# communication.net
KiCad netlist of a schematic drawn in Altium Designer
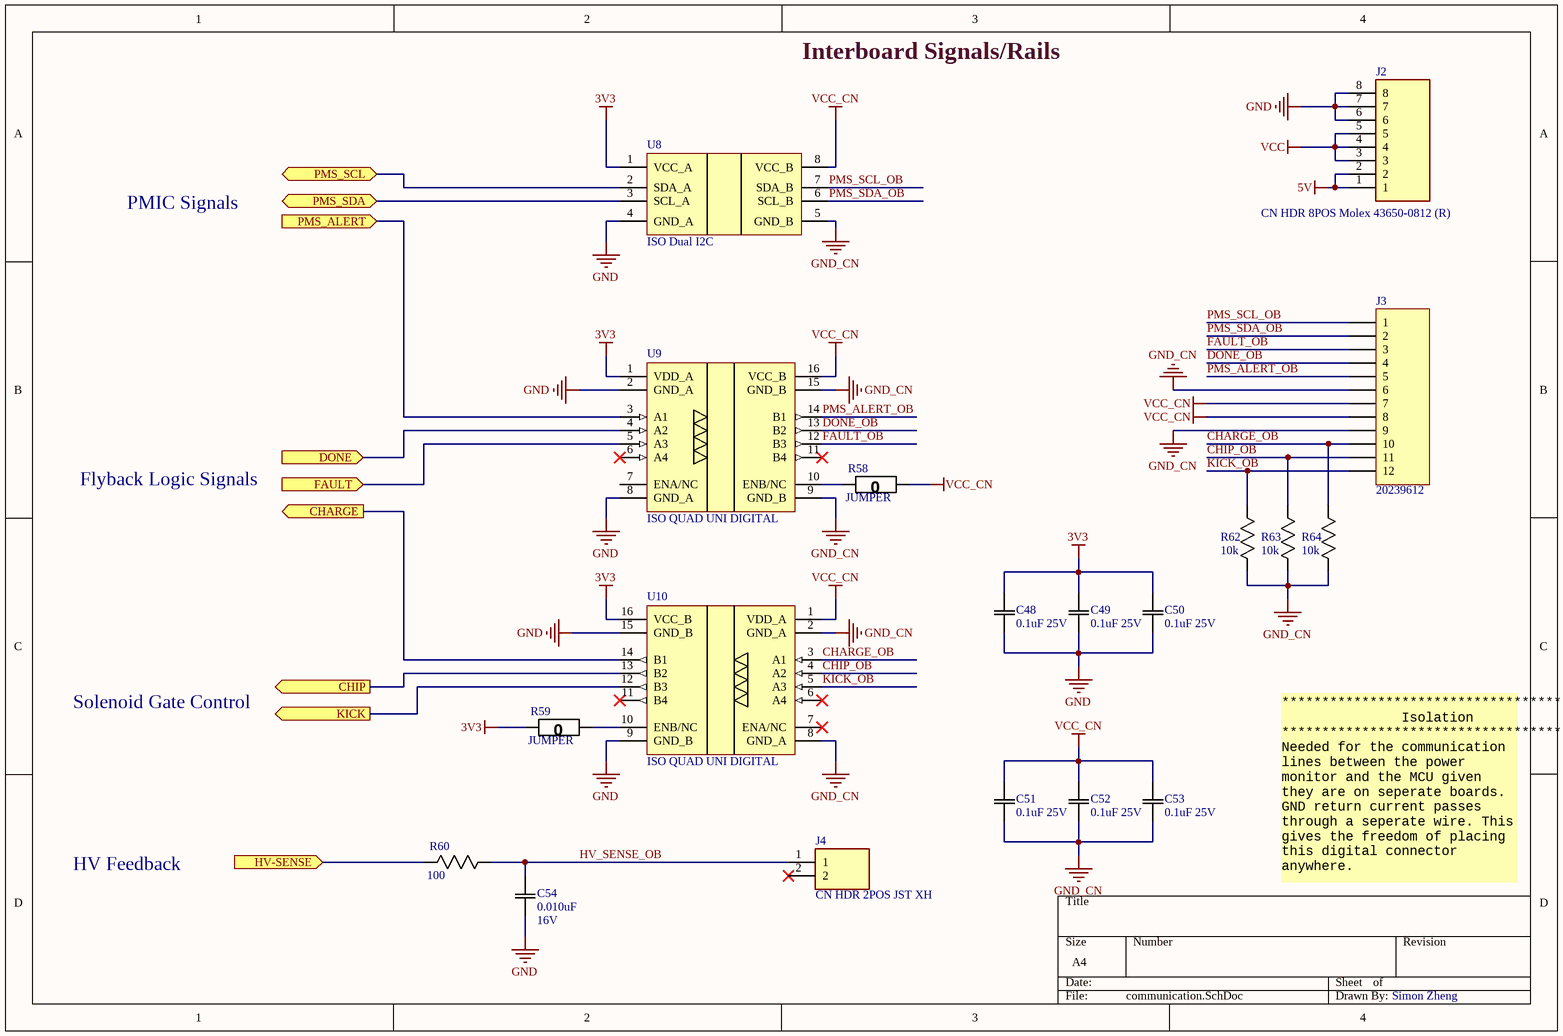
[diagram p0: communication.SchDoc]

(export (version "E")
  (design (tool "Eeschema 10.0.6"))
  (components
    (comp (ref "C48")
      (value "0.1uF 25V")
      (footprint "0805")
      (description "CAP CER 0.1UF 25V X7R 0805")
      (fields (field (name "TOLERANCE") "10%"))
      (libsource (lib "AltiumLibraries") (part "CAP 0.1uF 25V"))
    )
    (comp (ref "C49")
      (value "0.1uF 25V")
      (footprint "0805")
      (description "CAP CER 0.1UF 25V X7R 0805")
      (fields (field (name "TOLERANCE") "10%"))
      (libsource (lib "AltiumLibraries") (part "CAP 0.1uF 25V"))
    )
    (comp (ref "C50")
      (value "0.1uF 25V")
      (footprint "0805")
      (description "CAP CER 0.1UF 25V X7R 0805")
      (fields (field (name "TOLERANCE") "10%"))
      (libsource (lib "AltiumLibraries") (part "CAP 0.1uF 25V"))
    )
    (comp (ref "C51")
      (value "0.1uF 25V")
      (footprint "0805")
      (description "CAP CER 0.1UF 25V X7R 0805")
      (fields (field (name "TOLERANCE") "10%"))
      (libsource (lib "AltiumLibraries") (part "CAP 0.1uF 25V"))
    )
    (comp (ref "C52")
      (value "0.1uF 25V")
      (footprint "0805")
      (description "CAP CER 0.1UF 25V X7R 0805")
      (fields (field (name "TOLERANCE") "10%"))
      (libsource (lib "AltiumLibraries") (part "CAP 0.1uF 25V"))
    )
    (comp (ref "C53")
      (value "0.1uF 25V")
      (footprint "0805")
      (description "CAP CER 0.1UF 25V X7R 0805")
      (fields (field (name "TOLERANCE") "10%"))
      (libsource (lib "AltiumLibraries") (part "CAP 0.1uF 25V"))
    )
    (comp (ref "C54")
      (value "0.010uF")
      (footprint "0805")
      (description "CAP CER 0.010UF 16V X5R 0603/0805")
      (fields (field (name "TOLERANCE") "10%") (field (name "RATING") "16V"))
      (libsource (lib "AltiumLibraries") (part "CAP 0.010uF 16V"))
    )
    (comp (ref "J2")
      (value "CN HDR 8POS Molex 43650-0812 (R)")
      (footprint "CN 43650-0812")
      (description "Molex 43650-0812 8POS Microfit\r\nsingle row, right angle, surface mount")
      (libsource (lib "AltiumLibraries") (part "CN HDR 8POS Molex 43650-0812 (R)"))
    )
    (comp (ref "J3")
      (value "20239612")
      (footprint "CN 20239612")
      (description "12 POS Right Angle Pico Clasp Surface Mount")
      (libsource (lib "AltiumLibraries") (part "CN Pico Clasp 12POS"))
    )
    (comp (ref "J4")
      (value "CN HDR 2POS JST XH")
      (footprint "JST_S2B-XH-A(LF)(SN)")
      (description "Connector Header Through Hole 2 position 0.098 _2.50mm_\r\nJST XH")
      (fields (field (name "MP") "B2B-XH-A_LF__SN_") (field (name "MF") "JST Sales"))
      (libsource (lib "AltiumLibraries") (part "CN HDR 2POS JST XH"))
    )
    (comp (ref "R58")
      (value "JUMPER")
      (footprint "0805")
      (description "RES SMD 0 OHM JUMPER GENERIC 0805")
      (libsource (lib "AltiumLibraries") (part "RES 0 JUMPER"))
    )
    (comp (ref "R59")
      (value "JUMPER")
      (footprint "0805")
      (description "RES SMD 0 OHM JUMPER GENERIC 0805")
      (libsource (lib "AltiumLibraries") (part "RES 0 JUMPER"))
    )
    (comp (ref "R60")
      (value "100")
      (footprint "0805")
      (description "RES SMD 100 OHM 5% 1/8W 0805")
      (fields (field (name "TOLERANCE") "5%"))
      (libsource (lib "AltiumLibraries") (part "RES 100.0 1/8W"))
    )
    (comp (ref "R62")
      (value "10k")
      (footprint "0805")
      (description "RES SMD 10K OHM 1% 1/8W 0805")
      (fields (field (name "TOLERANCE") "1%"))
      (libsource (lib "") (part "RES 10k 1/8W - 1%_1"))
    )
    (comp (ref "R63")
      (value "10k")
      (footprint "0805")
      (description "RES SMD 10K OHM 1% 1/8W 0805")
      (fields (field (name "TOLERANCE") "1%"))
      (libsource (lib "AltiumLibraries") (part "RES 10k 1/8W - 1%"))
    )
    (comp (ref "R64")
      (value "10k")
      (footprint "0805")
      (description "RES SMD 10K OHM 1% 1/8W 0805")
      (fields (field (name "TOLERANCE") "1%"))
      (libsource (lib "AltiumLibraries") (part "RES 10k 1/8W - 1%"))
    )
    (comp (ref "U8")
      (value "ISO Dual I2C")
      (footprint "SOIC127P600X175-8N")
      (description "Digital Isolation Dual Ch Bidirectional I2C")
      (libsource (lib "AltiumLibraries") (part "ISO Dual I2C"))
    )
    (comp (ref "U9")
      (value "ISO QUAD UNI DIGITAL")
      (footprint "SOIC127P600X175-16N")
      (description "Digital Isolation Quad Channel.")
      (libsource (lib "") (part "ISO QUAD UNI DIGITAL_1"))
    )
    (comp (ref "U10")
      (value "ISO QUAD UNI DIGITAL")
      (footprint "SOIC127P600X175-16N")
      (description "Digital Isolation Quad Channel.")
      (libsource (lib "AltiumLibraries") (part "ISO QUAD UNI DIGITAL"))
    )
  )
  (nets
    (net (code "1") (name "/CHARGE") (class "Default")
      (node (ref "U10") (pin "14") (pinfunction "B1_14") (pintype "output"))
    )
    (net (code "2") (name "/CHARGE_OB") (class "Default")
      (node (ref "J3") (pin "10") (pinfunction "10_10") (pintype "passive"))
      (node (ref "R64") (pin "1") (pinfunction "R1_1") (pintype "passive"))
      (node (ref "U10") (pin "3") (pinfunction "A1_3") (pintype "input"))
    )
    (net (code "3") (name "/CHIP") (class "Default")
      (node (ref "U10") (pin "13") (pinfunction "B2_13") (pintype "output"))
    )
    (net (code "4") (name "/CHIP_OB") (class "Default")
      (node (ref "J3") (pin "11") (pinfunction "11_11") (pintype "passive"))
      (node (ref "R63") (pin "1") (pinfunction "R1_1") (pintype "passive"))
      (node (ref "U10") (pin "4") (pinfunction "A2_4") (pintype "input"))
    )
    (net (code "5") (name "/DONE") (class "Default")
      (node (ref "U9") (pin "4") (pinfunction "A2_4") (pintype "input"))
    )
    (net (code "6") (name "/DONE_OB") (class "Default")
      (node (ref "J3") (pin "4") (pinfunction "4_4") (pintype "passive"))
      (node (ref "U9") (pin "13") (pinfunction "B2_13") (pintype "output"))
    )
    (net (code "7") (name "/FAULT") (class "Default")
      (node (ref "U9") (pin "5") (pinfunction "A3_5") (pintype "input"))
    )
    (net (code "8") (name "/FAULT_OB") (class "Default")
      (node (ref "J3") (pin "3") (pinfunction "3_3") (pintype "passive"))
      (node (ref "U9") (pin "12") (pinfunction "B3_12") (pintype "output"))
    )
    (net (code "9") (name "/HV-SENSE") (class "Default")
      (node (ref "R60") (pin "2") (pinfunction "R2_2") (pintype "passive"))
    )
    (net (code "10") (name "/HV_SENSE_OB") (class "Default")
      (node (ref "C54") (pin "1") (pinfunction "C1_1") (pintype "passive"))
      (node (ref "J4") (pin "1") (pinfunction "1_1") (pintype "passive"))
      (node (ref "R60") (pin "1") (pinfunction "R1_1") (pintype "passive"))
    )
    (net (code "11") (name "/KICK") (class "Default")
      (node (ref "U10") (pin "12") (pinfunction "B3_12") (pintype "output"))
    )
    (net (code "12") (name "/KICK_OB") (class "Default")
      (node (ref "J3") (pin "12") (pinfunction "12_12") (pintype "passive"))
      (node (ref "R62") (pin "1") (pinfunction "R1_1") (pintype "passive"))
      (node (ref "U10") (pin "5") (pinfunction "A3_5") (pintype "input"))
    )
    (net (code "13") (name "/PMS_ALERT") (class "Default")
      (node (ref "U9") (pin "3") (pinfunction "A1_3") (pintype "input"))
    )
    (net (code "14") (name "/PMS_ALERT_OB") (class "Default")
      (node (ref "J3") (pin "5") (pinfunction "5_5") (pintype "passive"))
      (node (ref "U9") (pin "14") (pinfunction "B1_14") (pintype "output"))
    )
    (net (code "15") (name "/PMS_SCL") (class "Default")
      (node (ref "U8") (pin "2") (pinfunction "SDA_A_2") (pintype "passive"))
    )
    (net (code "16") (name "/PMS_SCL_OB") (class "Default")
      (node (ref "J3") (pin "1") (pinfunction "1_1") (pintype "passive"))
      (node (ref "U8") (pin "7") (pinfunction "SDA_B_7") (pintype "passive"))
    )
    (net (code "17") (name "/PMS_SDA") (class "Default")
      (node (ref "U8") (pin "3") (pinfunction "SCL_A_3") (pintype "passive"))
    )
    (net (code "18") (name "/PMS_SDA_OB") (class "Default")
      (node (ref "J3") (pin "2") (pinfunction "2_2") (pintype "passive"))
      (node (ref "U8") (pin "6") (pinfunction "SCL_B_6") (pintype "passive"))
    )
    (net (code "19") (name "3V3") (class "Default")
      (node (ref "C48") (pin "1") (pinfunction "C1_1") (pintype "passive"))
      (node (ref "C49") (pin "1") (pinfunction "C1_1") (pintype "passive"))
      (node (ref "C50") (pin "1") (pinfunction "C1_1") (pintype "passive"))
      (node (ref "R59") (pin "2") (pinfunction "R2_2") (pintype "passive"))
      (node (ref "U10") (pin "16") (pinfunction "VCC_B_16") (pintype "passive"))
      (node (ref "U8") (pin "1") (pinfunction "VCC_A_1") (pintype "passive"))
      (node (ref "U9") (pin "1") (pinfunction "VDD_A_1") (pintype "passive"))
    )
    (net (code "20") (name "5V") (class "Default")
      (node (ref "J2") (pin "1") (pinfunction "1_1") (pintype "passive"))
      (node (ref "J2") (pin "2") (pinfunction "2_2") (pintype "passive"))
    )
    (net (code "21") (name "GND") (class "Default")
      (node (ref "C48") (pin "2") (pinfunction "C2_2") (pintype "passive"))
      (node (ref "C49") (pin "2") (pinfunction "C2_2") (pintype "passive"))
      (node (ref "C50") (pin "2") (pinfunction "C2_2") (pintype "passive"))
      (node (ref "C54") (pin "2") (pinfunction "C2_2") (pintype "passive"))
      (node (ref "J2") (pin "6") (pinfunction "6_6") (pintype "passive"))
      (node (ref "J2") (pin "7") (pinfunction "7_7") (pintype "passive"))
      (node (ref "J2") (pin "8") (pinfunction "8_8") (pintype "passive"))
      (node (ref "U10") (pin "15") (pinfunction "GND_B_15") (pintype "passive"))
      (node (ref "U10") (pin "9") (pinfunction "GND_B_9") (pintype "passive"))
      (node (ref "U8") (pin "4") (pinfunction "GND_A_4") (pintype "passive"))
      (node (ref "U9") (pin "2") (pinfunction "GND_A_2") (pintype "passive"))
      (node (ref "U9") (pin "8") (pinfunction "GND_A_8") (pintype "passive"))
    )
    (net (code "22") (name "GND_CN") (class "Default")
      (node (ref "C51") (pin "2") (pinfunction "C2_2") (pintype "passive"))
      (node (ref "C52") (pin "2") (pinfunction "C2_2") (pintype "passive"))
      (node (ref "C53") (pin "2") (pinfunction "C2_2") (pintype "passive"))
      (node (ref "J3") (pin "6") (pinfunction "6_6") (pintype "passive"))
      (node (ref "J3") (pin "9") (pinfunction "9_9") (pintype "passive"))
      (node (ref "R62") (pin "2") (pinfunction "R2_2") (pintype "passive"))
      (node (ref "R63") (pin "2") (pinfunction "R2_2") (pintype "passive"))
      (node (ref "R64") (pin "2") (pinfunction "R2_2") (pintype "passive"))
      (node (ref "U10") (pin "2") (pinfunction "GND_A_2") (pintype "passive"))
      (node (ref "U10") (pin "8") (pinfunction "GND_A_8") (pintype "passive"))
      (node (ref "U8") (pin "5") (pinfunction "GND_B_5") (pintype "passive"))
      (node (ref "U9") (pin "15") (pinfunction "GND_B_15") (pintype "passive"))
      (node (ref "U9") (pin "9") (pinfunction "GND_B_9") (pintype "passive"))
    )
    (net (code "23") (name "Net-(R58-R2)") (class "Default")
      (node (ref "R58") (pin "2") (pinfunction "R2_2") (pintype "passive"))
      (node (ref "U9") (pin "10") (pinfunction "ENB/NC_10") (pintype "passive"))
    )
    (net (code "24") (name "Net-(R59-R1)") (class "Default")
      (node (ref "R59") (pin "1") (pinfunction "R1_1") (pintype "passive"))
      (node (ref "U10") (pin "10") (pinfunction "ENB/NC_10") (pintype "passive"))
    )
    (net (code "25") (name "VCC") (class "Default")
      (node (ref "J2") (pin "3") (pinfunction "3_3") (pintype "passive"))
      (node (ref "J2") (pin "4") (pinfunction "4_4") (pintype "passive"))
      (node (ref "J2") (pin "5") (pinfunction "5_5") (pintype "passive"))
    )
    (net (code "26") (name "VCC_CN") (class "Default")
      (node (ref "C51") (pin "1") (pinfunction "C1_1") (pintype "passive"))
      (node (ref "C52") (pin "1") (pinfunction "C1_1") (pintype "passive"))
      (node (ref "C53") (pin "1") (pinfunction "C1_1") (pintype "passive"))
      (node (ref "J3") (pin "7") (pinfunction "7_7") (pintype "passive"))
      (node (ref "J3") (pin "8") (pinfunction "8_8") (pintype "passive"))
      (node (ref "R58") (pin "1") (pinfunction "R1_1") (pintype "passive"))
      (node (ref "U10") (pin "1") (pinfunction "VDD_A_1") (pintype "passive"))
      (node (ref "U8") (pin "8") (pinfunction "VCC_B_8") (pintype "passive"))
      (node (ref "U9") (pin "16") (pinfunction "VCC_B_16") (pintype "passive"))
    )
    (net (code "27") (name "unconnected-(J4-Pad2)") (class "Default")
      (node (ref "J4") (pin "2") (pinfunction "2_2") (pintype "passive+no_connect"))
    )
    (net (code "28") (name "unconnected-(U9-A4-Pad6)") (class "Default")
      (node (ref "U9") (pin "6") (pinfunction "A4_6") (pintype "input+no_connect"))
    )
    (net (code "29") (name "unconnected-(U9-B4-Pad11)") (class "Default")
      (node (ref "U9") (pin "11") (pinfunction "B4_11") (pintype "output+no_connect"))
    )
    (net (code "30") (name "unconnected-(U9-ENA{slash}NC-Pad7)") (class "Default")
      (node (ref "U9") (pin "7") (pinfunction "ENA/NC_7") (pintype "passive"))
    )
    (net (code "31") (name "unconnected-(U10-A4-Pad6)") (class "Default")
      (node (ref "U10") (pin "6") (pinfunction "A4_6") (pintype "input+no_connect"))
    )
    (net (code "32") (name "unconnected-(U10-B4-Pad11)") (class "Default")
      (node (ref "U10") (pin "11") (pinfunction "B4_11") (pintype "output+no_connect"))
    )
    (net (code "33") (name "unconnected-(U10-ENA{slash}NC-Pad7)") (class "Default")
      (node (ref "U10") (pin "7") (pinfunction "ENA/NC_7") (pintype "passive+no_connect"))
    )
  )
)
